# PCB_v_2_2021.net
KiCad netlist of a schematic drawn in EAGLE
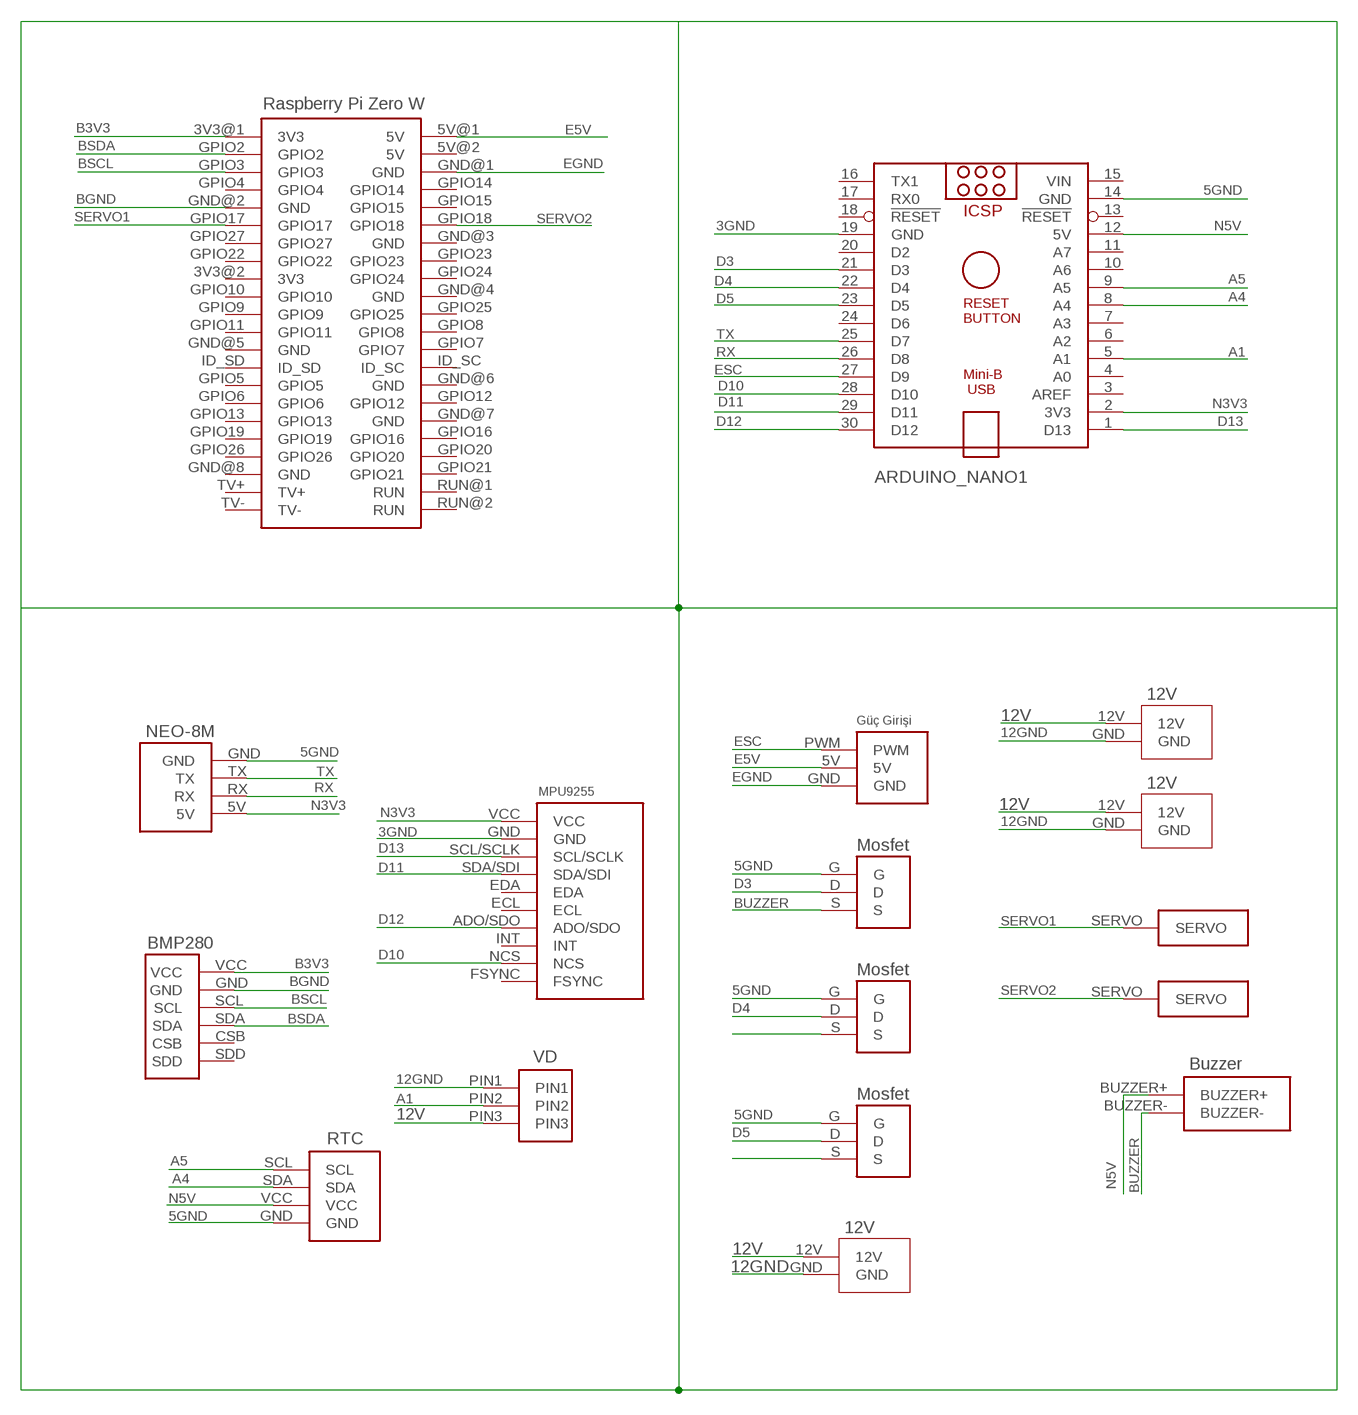
[diagram p0: schematic, sheet 1]

(export (version "E")
  (design (tool "Eeschema 10.0.6"))
  (components
    (comp (ref "ARDUINO_NANO1")
      (value "ARDUINO_NANO")
      (footprint "eagle-import:ARDUINO_NANO")
      (libsource (lib "eagle-import") (part "ARDUINO_NANO"))
    )
    (comp (ref "BMP1")
      (value "BMP280")
      (footprint "eagle-import:BMP280")
      (libsource (lib "eagle-import") (part "BMP280"))
    )
    (comp (ref "RPIZEROW1")
      (value "RASPBERRY_ZERO_W")
      (footprint "eagle-import:RASPBERRY_ZERO_W")
      (libsource (lib "eagle-import") (part "RASPBERRY_ZERO_W"))
    )
    (comp (ref "U$1")
      (value "NEOM8N")
      (footprint "eagle-import:NEO8M")
      (libsource (lib "eagle-import") (part "NEOM8N"))
    )
    (comp (ref "U$2")
      (value "MPU9255")
      (footprint "eagle-import:MPU9255")
      (libsource (lib "eagle-import") (part "MPU9255"))
    )
    (comp (ref "U$3")
      (value "VOLTAGE_DIVIDER")
      (footprint "eagle-import:VOLTAGE_DIVIDER")
      (libsource (lib "eagle-import") (part "VOLTAGE_DIVIDER"))
    )
    (comp (ref "U$4")
      (value "ESC_GIRIS")
      (footprint "eagle-import:ESC_GIRIS")
      (libsource (lib "eagle-import") (part "ESC_GIRIS"))
    )
    (comp (ref "U$5")
      (value "12V")
      (footprint "eagle-import:12V")
      (libsource (lib "eagle-import") (part "12V"))
    )
    (comp (ref "U$6")
      (value "12V")
      (footprint "eagle-import:12V")
      (libsource (lib "eagle-import") (part "12V"))
    )
    (comp (ref "U$7")
      (value "MOSFET")
      (footprint "eagle-import:MOSFET")
      (libsource (lib "eagle-import") (part "MOSFET"))
    )
    (comp (ref "U$8")
      (value "MOSFET")
      (footprint "eagle-import:MOSFET")
      (libsource (lib "eagle-import") (part "MOSFET"))
    )
    (comp (ref "U$9")
      (value "MOSFET")
      (footprint "eagle-import:MOSFET")
      (libsource (lib "eagle-import") (part "MOSFET"))
    )
    (comp (ref "U$10")
      (value "RTC")
      (footprint "eagle-import:RTC")
      (libsource (lib "eagle-import") (part "RTC"))
    )
    (comp (ref "U$11")
      (value "SERVO_SIGNAL")
      (footprint "eagle-import:SERVO_SIGNAL")
      (libsource (lib "eagle-import") (part "SERVO_SIGNAL"))
    )
    (comp (ref "U$12")
      (value "SERVO_SIGNAL")
      (footprint "eagle-import:SERVO_SIGNAL")
      (libsource (lib "eagle-import") (part "SERVO_SIGNAL"))
    )
    (comp (ref "U$13")
      (value "12V")
      (footprint "eagle-import:12V")
      (libsource (lib "eagle-import") (part "12V"))
    )
    (comp (ref "U$14")
      (value "BUZZER")
      (footprint "eagle-import:BUZZER")
      (libsource (lib "eagle-import") (part "BUZZER"))
    )
  )
  (nets
    (net (code "1") (name "/3GND") (class "Default")
      (node (ref "ARDUINO_NANO1") (pin "19") (pinfunction "GND_19") (pintype "power_in"))
      (node (ref "U$2") (pin "GND") (pinfunction "GND_GND") (pintype "bidirectional"))
    )
    (net (code "2") (name "/5GND") (class "Default")
      (node (ref "ARDUINO_NANO1") (pin "14") (pinfunction "GND_14") (pintype "power_in"))
      (node (ref "U$1") (pin "GND") (pinfunction "GND_GND") (pintype "bidirectional"))
      (node (ref "U$10") (pin "GND") (pinfunction "GND_GND") (pintype "bidirectional"))
      (node (ref "U$7") (pin "G") (pinfunction "G_G") (pintype "bidirectional"))
      (node (ref "U$8") (pin "G") (pinfunction "G_G") (pintype "bidirectional"))
      (node (ref "U$9") (pin "G") (pinfunction "G_G") (pintype "bidirectional"))
    )
    (net (code "3") (name "/12GND") (class "Default")
      (node (ref "U$13") (pin "GND") (pinfunction "GND_GND") (pintype "bidirectional"))
      (node (ref "U$3") (pin "PIN1") (pinfunction "PIN1_PIN1") (pintype "bidirectional"))
      (node (ref "U$5") (pin "GND") (pinfunction "GND_GND") (pintype "bidirectional"))
      (node (ref "U$6") (pin "GND") (pinfunction "GND_GND") (pintype "bidirectional"))
    )
    (net (code "4") (name "/12V") (class "Default")
      (node (ref "U$13") (pin "12V") (pinfunction "12V_12V") (pintype "bidirectional"))
      (node (ref "U$3") (pin "PIN3") (pinfunction "PIN3_PIN3") (pintype "bidirectional"))
      (node (ref "U$5") (pin "12V") (pinfunction "12V_12V") (pintype "bidirectional"))
      (node (ref "U$6") (pin "12V") (pinfunction "12V_12V") (pintype "bidirectional"))
    )
    (net (code "5") (name "/A1") (class "Default")
      (node (ref "ARDUINO_NANO1") (pin "5") (pinfunction "A1_5") (pintype "bidirectional"))
      (node (ref "U$3") (pin "PIN2") (pinfunction "PIN2_PIN2") (pintype "bidirectional"))
    )
    (net (code "6") (name "/A4") (class "Default")
      (node (ref "ARDUINO_NANO1") (pin "8") (pinfunction "A4_8") (pintype "bidirectional"))
      (node (ref "U$10") (pin "SDA") (pinfunction "SDA_SDA") (pintype "bidirectional"))
    )
    (net (code "7") (name "/A5") (class "Default")
      (node (ref "ARDUINO_NANO1") (pin "9") (pinfunction "A5_9") (pintype "bidirectional"))
      (node (ref "U$10") (pin "SCL") (pinfunction "SCL_SCL") (pintype "bidirectional"))
    )
    (net (code "8") (name "/B3V3") (class "Default")
      (node (ref "BMP1") (pin "VCC") (pinfunction "VCC_VCC") (pintype "bidirectional"))
      (node (ref "RPIZEROW1") (pin "3V3@1") (pinfunction "3V3_3V3@1") (pintype "bidirectional"))
    )
    (net (code "9") (name "/BGND") (class "Default")
      (node (ref "BMP1") (pin "GND") (pinfunction "GND_GND") (pintype "bidirectional"))
      (node (ref "RPIZEROW1") (pin "GND@2") (pinfunction "GND_GND@2") (pintype "bidirectional"))
    )
    (net (code "10") (name "/BSCL") (class "Default")
      (node (ref "BMP1") (pin "SCL") (pinfunction "SCL_SCL") (pintype "bidirectional"))
      (node (ref "RPIZEROW1") (pin "GPIO3") (pinfunction "GPIO3_GPIO3") (pintype "bidirectional"))
    )
    (net (code "11") (name "/BSDA") (class "Default")
      (node (ref "BMP1") (pin "SDA") (pinfunction "SDA_SDA") (pintype "bidirectional"))
      (node (ref "RPIZEROW1") (pin "GPIO2") (pinfunction "GPIO2_GPIO2") (pintype "bidirectional"))
    )
    (net (code "12") (name "/BUZZER") (class "Default")
      (node (ref "U$14") (pin "BUZZER-") (pinfunction "BUZZER-_BUZZER-") (pintype "bidirectional"))
      (node (ref "U$7") (pin "S") (pinfunction "S_S") (pintype "bidirectional"))
    )
    (net (code "13") (name "/D3") (class "Default")
      (node (ref "ARDUINO_NANO1") (pin "21") (pinfunction "D3_21") (pintype "bidirectional"))
      (node (ref "U$7") (pin "D") (pinfunction "D_D") (pintype "bidirectional"))
    )
    (net (code "14") (name "/D4") (class "Default")
      (node (ref "ARDUINO_NANO1") (pin "22") (pinfunction "D4_22") (pintype "bidirectional"))
      (node (ref "U$8") (pin "D") (pinfunction "D_D") (pintype "bidirectional"))
    )
    (net (code "15") (name "/D5") (class "Default")
      (node (ref "ARDUINO_NANO1") (pin "23") (pinfunction "D5_23") (pintype "bidirectional"))
      (node (ref "U$9") (pin "D") (pinfunction "D_D") (pintype "bidirectional"))
    )
    (net (code "16") (name "/D10") (class "Default")
      (node (ref "ARDUINO_NANO1") (pin "28") (pinfunction "D10_28") (pintype "bidirectional"))
      (node (ref "U$2") (pin "NCS") (pinfunction "NCS_NCS") (pintype "bidirectional"))
    )
    (net (code "17") (name "/D11") (class "Default")
      (node (ref "ARDUINO_NANO1") (pin "29") (pinfunction "D11_29") (pintype "bidirectional"))
      (node (ref "U$2") (pin "SDA/SDI") (pinfunction "SDA/SDI_SDA/SDI") (pintype "bidirectional"))
    )
    (net (code "18") (name "/D12") (class "Default")
      (node (ref "ARDUINO_NANO1") (pin "30") (pinfunction "D12_30") (pintype "bidirectional"))
      (node (ref "U$2") (pin "ADO/SDO") (pinfunction "ADO/SDO_ADO/SDO") (pintype "bidirectional"))
    )
    (net (code "19") (name "/D13") (class "Default")
      (node (ref "ARDUINO_NANO1") (pin "1") (pinfunction "D13_1") (pintype "bidirectional"))
      (node (ref "U$2") (pin "SCL/SCLK") (pinfunction "SCL/SCLK_SCL/SCLK") (pintype "bidirectional"))
    )
    (net (code "20") (name "/E5V") (class "Default")
      (node (ref "RPIZEROW1") (pin "5V@1") (pinfunction "5V_5V@1") (pintype "bidirectional"))
      (node (ref "U$4") (pin "5V") (pinfunction "5V_5V") (pintype "bidirectional"))
    )
    (net (code "21") (name "/EGND") (class "Default")
      (node (ref "RPIZEROW1") (pin "GND@1") (pinfunction "GND_GND@1") (pintype "bidirectional"))
      (node (ref "U$4") (pin "GND") (pinfunction "GND_GND") (pintype "bidirectional"))
    )
    (net (code "22") (name "/ESC") (class "Default")
      (node (ref "ARDUINO_NANO1") (pin "27") (pinfunction "D9_27") (pintype "bidirectional"))
      (node (ref "U$4") (pin "PWM") (pinfunction "PWM_PWM") (pintype "bidirectional"))
    )
    (net (code "23") (name "/N3V3") (class "Default")
      (node (ref "ARDUINO_NANO1") (pin "2") (pinfunction "3V3_2") (pintype "output"))
      (node (ref "U$1") (pin "5V") (pinfunction "5V_5V") (pintype "bidirectional"))
      (node (ref "U$2") (pin "VCC") (pinfunction "VCC_VCC") (pintype "bidirectional"))
    )
    (net (code "24") (name "/N5V") (class "Default")
      (node (ref "ARDUINO_NANO1") (pin "12") (pinfunction "5V_12") (pintype "power_in"))
      (node (ref "U$10") (pin "VCC") (pinfunction "VCC_VCC") (pintype "bidirectional"))
      (node (ref "U$14") (pin "BUZZER+") (pinfunction "BUZZER+_BUZZER+") (pintype "bidirectional"))
    )
    (net (code "25") (name "/RX") (class "Default")
      (node (ref "ARDUINO_NANO1") (pin "26") (pinfunction "D8_26") (pintype "bidirectional"))
      (node (ref "U$1") (pin "RX") (pinfunction "RX_RX") (pintype "bidirectional"))
    )
    (net (code "26") (name "/SERVO1") (class "Default")
      (node (ref "RPIZEROW1") (pin "GPIO17") (pinfunction "GPIO17_GPIO17") (pintype "bidirectional"))
      (node (ref "U$11") (pin "SERVO") (pinfunction "SERVO_SERVO") (pintype "bidirectional"))
    )
    (net (code "27") (name "/SERVO2") (class "Default")
      (node (ref "RPIZEROW1") (pin "GPIO18") (pinfunction "GPIO18_GPIO18") (pintype "bidirectional"))
      (node (ref "U$12") (pin "SERVO") (pinfunction "SERVO_SERVO") (pintype "bidirectional"))
    )
    (net (code "28") (name "/TX") (class "Default")
      (node (ref "ARDUINO_NANO1") (pin "25") (pinfunction "D7_25") (pintype "bidirectional"))
      (node (ref "U$1") (pin "TX") (pinfunction "TX_TX") (pintype "bidirectional"))
    )
    (net (code "29") (name "/VIN") (class "Default")
      (node (ref "ARDUINO_NANO1") (pin "15") (pinfunction "VIN_15") (pintype "power_in"))
    )
    (net (code "30") (name "unconnected-(ARDUINO_NANO1-A0-Pad4)") (class "Default")
      (node (ref "ARDUINO_NANO1") (pin "4") (pinfunction "A0_4") (pintype "bidirectional"))
    )
    (net (code "31") (name "unconnected-(ARDUINO_NANO1-A2-Pad6)") (class "Default")
      (node (ref "ARDUINO_NANO1") (pin "6") (pinfunction "A2_6") (pintype "bidirectional"))
    )
    (net (code "32") (name "unconnected-(ARDUINO_NANO1-A3-Pad7)") (class "Default")
      (node (ref "ARDUINO_NANO1") (pin "7") (pinfunction "A3_7") (pintype "bidirectional"))
    )
    (net (code "33") (name "unconnected-(ARDUINO_NANO1-A6-Pad10)") (class "Default")
      (node (ref "ARDUINO_NANO1") (pin "10") (pinfunction "A6_10") (pintype "bidirectional"))
    )
    (net (code "34") (name "unconnected-(ARDUINO_NANO1-A7-Pad11)") (class "Default")
      (node (ref "ARDUINO_NANO1") (pin "11") (pinfunction "A7_11") (pintype "bidirectional"))
    )
    (net (code "35") (name "unconnected-(ARDUINO_NANO1-AREF-Pad3)") (class "Default")
      (node (ref "ARDUINO_NANO1") (pin "3") (pinfunction "AREF_3") (pintype "input"))
    )
    (net (code "36") (name "unconnected-(ARDUINO_NANO1-D2-Pad20)") (class "Default")
      (node (ref "ARDUINO_NANO1") (pin "20") (pinfunction "D2_20") (pintype "bidirectional"))
    )
    (net (code "37") (name "unconnected-(ARDUINO_NANO1-D6-Pad24)") (class "Default")
      (node (ref "ARDUINO_NANO1") (pin "24") (pinfunction "D6_24") (pintype "bidirectional"))
    )
    (net (code "38") (name "unconnected-(ARDUINO_NANO1-RX0-Pad17)") (class "Default")
      (node (ref "ARDUINO_NANO1") (pin "17") (pinfunction "RX0_17") (pintype "bidirectional"))
    )
    (net (code "39") (name "unconnected-(ARDUINO_NANO1-TX1-Pad16)") (class "Default")
      (node (ref "ARDUINO_NANO1") (pin "16") (pinfunction "TX1_16") (pintype "bidirectional"))
    )
    (net (code "40") (name "unconnected-(ARDUINO_NANO1-~{RESET}-Pad13)") (class "Default")
      (node (ref "ARDUINO_NANO1") (pin "13") (pinfunction "~{RESET}_13") (pintype "input"))
    )
    (net (code "41") (name "unconnected-(ARDUINO_NANO1-~{RESET}-Pad18)") (class "Default")
      (node (ref "ARDUINO_NANO1") (pin "18") (pinfunction "~{RESET}_18") (pintype "input"))
    )
    (net (code "42") (name "unconnected-(BMP1-PadCSB)") (class "Default")
      (node (ref "BMP1") (pin "CSB") (pinfunction "CSB_CSB") (pintype "bidirectional"))
    )
    (net (code "43") (name "unconnected-(BMP1-PadSDD)") (class "Default")
      (node (ref "BMP1") (pin "SDD") (pinfunction "SDD_SDD") (pintype "bidirectional"))
    )
    (net (code "44") (name "unconnected-(RPIZEROW1-3V3-Pad3V3@2)") (class "Default")
      (node (ref "RPIZEROW1") (pin "3V3@2") (pinfunction "3V3_3V3@2") (pintype "bidirectional"))
    )
    (net (code "45") (name "unconnected-(RPIZEROW1-5V-Pad5V@2)") (class "Default")
      (node (ref "RPIZEROW1") (pin "5V@2") (pinfunction "5V_5V@2") (pintype "bidirectional"))
    )
    (net (code "46") (name "unconnected-(RPIZEROW1-GND-PadGND@3)") (class "Default")
      (node (ref "RPIZEROW1") (pin "GND@3") (pinfunction "GND_GND@3") (pintype "bidirectional"))
    )
    (net (code "47") (name "unconnected-(RPIZEROW1-GND-PadGND@4)") (class "Default")
      (node (ref "RPIZEROW1") (pin "GND@4") (pinfunction "GND_GND@4") (pintype "bidirectional"))
    )
    (net (code "48") (name "unconnected-(RPIZEROW1-GND-PadGND@5)") (class "Default")
      (node (ref "RPIZEROW1") (pin "GND@5") (pinfunction "GND_GND@5") (pintype "bidirectional"))
    )
    (net (code "49") (name "unconnected-(RPIZEROW1-GND-PadGND@6)") (class "Default")
      (node (ref "RPIZEROW1") (pin "GND@6") (pinfunction "GND_GND@6") (pintype "bidirectional"))
    )
    (net (code "50") (name "unconnected-(RPIZEROW1-GND-PadGND@7)") (class "Default")
      (node (ref "RPIZEROW1") (pin "GND@7") (pinfunction "GND_GND@7") (pintype "bidirectional"))
    )
    (net (code "51") (name "unconnected-(RPIZEROW1-GND-PadGND@8)") (class "Default")
      (node (ref "RPIZEROW1") (pin "GND@8") (pinfunction "GND_GND@8") (pintype "bidirectional"))
    )
    (net (code "52") (name "unconnected-(RPIZEROW1-PadGPIO4)") (class "Default")
      (node (ref "RPIZEROW1") (pin "GPIO4") (pinfunction "GPIO4_GPIO4") (pintype "bidirectional"))
    )
    (net (code "53") (name "unconnected-(RPIZEROW1-PadGPIO5)") (class "Default")
      (node (ref "RPIZEROW1") (pin "GPIO5") (pinfunction "GPIO5_GPIO5") (pintype "bidirectional"))
    )
    (net (code "54") (name "unconnected-(RPIZEROW1-PadGPIO6)") (class "Default")
      (node (ref "RPIZEROW1") (pin "GPIO6") (pinfunction "GPIO6_GPIO6") (pintype "bidirectional"))
    )
    (net (code "55") (name "unconnected-(RPIZEROW1-PadGPIO7)") (class "Default")
      (node (ref "RPIZEROW1") (pin "GPIO7") (pinfunction "GPIO7_GPIO7") (pintype "bidirectional"))
    )
    (net (code "56") (name "unconnected-(RPIZEROW1-PadGPIO8)") (class "Default")
      (node (ref "RPIZEROW1") (pin "GPIO8") (pinfunction "GPIO8_GPIO8") (pintype "bidirectional"))
    )
    (net (code "57") (name "unconnected-(RPIZEROW1-PadGPIO9)") (class "Default")
      (node (ref "RPIZEROW1") (pin "GPIO9") (pinfunction "GPIO9_GPIO9") (pintype "bidirectional"))
    )
    (net (code "58") (name "unconnected-(RPIZEROW1-PadGPIO10)") (class "Default")
      (node (ref "RPIZEROW1") (pin "GPIO10") (pinfunction "GPIO10_GPIO10") (pintype "bidirectional"))
    )
    (net (code "59") (name "unconnected-(RPIZEROW1-PadGPIO11)") (class "Default")
      (node (ref "RPIZEROW1") (pin "GPIO11") (pinfunction "GPIO11_GPIO11") (pintype "bidirectional"))
    )
    (net (code "60") (name "unconnected-(RPIZEROW1-PadGPIO12)") (class "Default")
      (node (ref "RPIZEROW1") (pin "GPIO12") (pinfunction "GPIO12_GPIO12") (pintype "bidirectional"))
    )
    (net (code "61") (name "unconnected-(RPIZEROW1-PadGPIO13)") (class "Default")
      (node (ref "RPIZEROW1") (pin "GPIO13") (pinfunction "GPIO13_GPIO13") (pintype "bidirectional"))
    )
    (net (code "62") (name "unconnected-(RPIZEROW1-PadGPIO14)") (class "Default")
      (node (ref "RPIZEROW1") (pin "GPIO14") (pinfunction "GPIO14_GPIO14") (pintype "bidirectional"))
    )
    (net (code "63") (name "unconnected-(RPIZEROW1-PadGPIO15)") (class "Default")
      (node (ref "RPIZEROW1") (pin "GPIO15") (pinfunction "GPIO15_GPIO15") (pintype "bidirectional"))
    )
    (net (code "64") (name "unconnected-(RPIZEROW1-PadGPIO16)") (class "Default")
      (node (ref "RPIZEROW1") (pin "GPIO16") (pinfunction "GPIO16_GPIO16") (pintype "bidirectional"))
    )
    (net (code "65") (name "unconnected-(RPIZEROW1-PadGPIO19)") (class "Default")
      (node (ref "RPIZEROW1") (pin "GPIO19") (pinfunction "GPIO19_GPIO19") (pintype "bidirectional"))
    )
    (net (code "66") (name "unconnected-(RPIZEROW1-PadGPIO20)") (class "Default")
      (node (ref "RPIZEROW1") (pin "GPIO20") (pinfunction "GPIO20_GPIO20") (pintype "bidirectional"))
    )
    (net (code "67") (name "unconnected-(RPIZEROW1-PadGPIO21)") (class "Default")
      (node (ref "RPIZEROW1") (pin "GPIO21") (pinfunction "GPIO21_GPIO21") (pintype "bidirectional"))
    )
    (net (code "68") (name "unconnected-(RPIZEROW1-PadGPIO22)") (class "Default")
      (node (ref "RPIZEROW1") (pin "GPIO22") (pinfunction "GPIO22_GPIO22") (pintype "bidirectional"))
    )
    (net (code "69") (name "unconnected-(RPIZEROW1-PadGPIO23)") (class "Default")
      (node (ref "RPIZEROW1") (pin "GPIO23") (pinfunction "GPIO23_GPIO23") (pintype "bidirectional"))
    )
    (net (code "70") (name "unconnected-(RPIZEROW1-PadGPIO24)") (class "Default")
      (node (ref "RPIZEROW1") (pin "GPIO24") (pinfunction "GPIO24_GPIO24") (pintype "bidirectional"))
    )
    (net (code "71") (name "unconnected-(RPIZEROW1-PadGPIO25)") (class "Default")
      (node (ref "RPIZEROW1") (pin "GPIO25") (pinfunction "GPIO25_GPIO25") (pintype "bidirectional"))
    )
    (net (code "72") (name "unconnected-(RPIZEROW1-PadGPIO26)") (class "Default")
      (node (ref "RPIZEROW1") (pin "GPIO26") (pinfunction "GPIO26_GPIO26") (pintype "bidirectional"))
    )
    (net (code "73") (name "unconnected-(RPIZEROW1-PadGPIO27)") (class "Default")
      (node (ref "RPIZEROW1") (pin "GPIO27") (pinfunction "GPIO27_GPIO27") (pintype "bidirectional"))
    )
    (net (code "74") (name "unconnected-(RPIZEROW1-PadID_SC)") (class "Default")
      (node (ref "RPIZEROW1") (pin "ID_SC") (pinfunction "ID_SC_ID_SC") (pintype "bidirectional"))
    )
    (net (code "75") (name "unconnected-(RPIZEROW1-PadID_SD)") (class "Default")
      (node (ref "RPIZEROW1") (pin "ID_SD") (pinfunction "ID_SD_ID_SD") (pintype "bidirectional"))
    )
    (net (code "76") (name "unconnected-(RPIZEROW1-PadTV+)") (class "Default")
      (node (ref "RPIZEROW1") (pin "TV+") (pinfunction "TV+_TV+") (pintype "bidirectional"))
    )
    (net (code "77") (name "unconnected-(RPIZEROW1-PadTV-)") (class "Default")
      (node (ref "RPIZEROW1") (pin "TV-") (pinfunction "TV-_TV-") (pintype "bidirectional"))
    )
    (net (code "78") (name "unconnected-(RPIZEROW1-RUN-PadRUN@1)") (class "Default")
      (node (ref "RPIZEROW1") (pin "RUN@1") (pinfunction "RUN_RUN@1") (pintype "bidirectional"))
    )
    (net (code "79") (name "unconnected-(RPIZEROW1-RUN-PadRUN@2)") (class "Default")
      (node (ref "RPIZEROW1") (pin "RUN@2") (pinfunction "RUN_RUN@2") (pintype "bidirectional"))
    )
    (net (code "80") (name "unconnected-(U$2-PadECL)") (class "Default")
      (node (ref "U$2") (pin "ECL") (pinfunction "ECL_ECL") (pintype "bidirectional"))
    )
    (net (code "81") (name "unconnected-(U$2-PadEDA)") (class "Default")
      (node (ref "U$2") (pin "EDA") (pinfunction "EDA_EDA") (pintype "bidirectional"))
    )
    (net (code "82") (name "unconnected-(U$2-PadFSYNC)") (class "Default")
      (node (ref "U$2") (pin "FSYNC") (pinfunction "FSYNC_FSYNC") (pintype "bidirectional"))
    )
    (net (code "83") (name "unconnected-(U$2-PadINT)") (class "Default")
      (node (ref "U$2") (pin "INT") (pinfunction "INT_INT") (pintype "bidirectional"))
    )
    (net (code "84") (name "unconnected-(U$8-PadS)") (class "Default")
      (node (ref "U$8") (pin "S") (pinfunction "S_S") (pintype "bidirectional"))
    )
    (net (code "85") (name "unconnected-(U$9-PadS)") (class "Default")
      (node (ref "U$9") (pin "S") (pinfunction "S_S") (pintype "bidirectional"))
    )
  )
)
